# adapter_pcb.net
KiCad netlist of a schematic drawn in Altium Designer
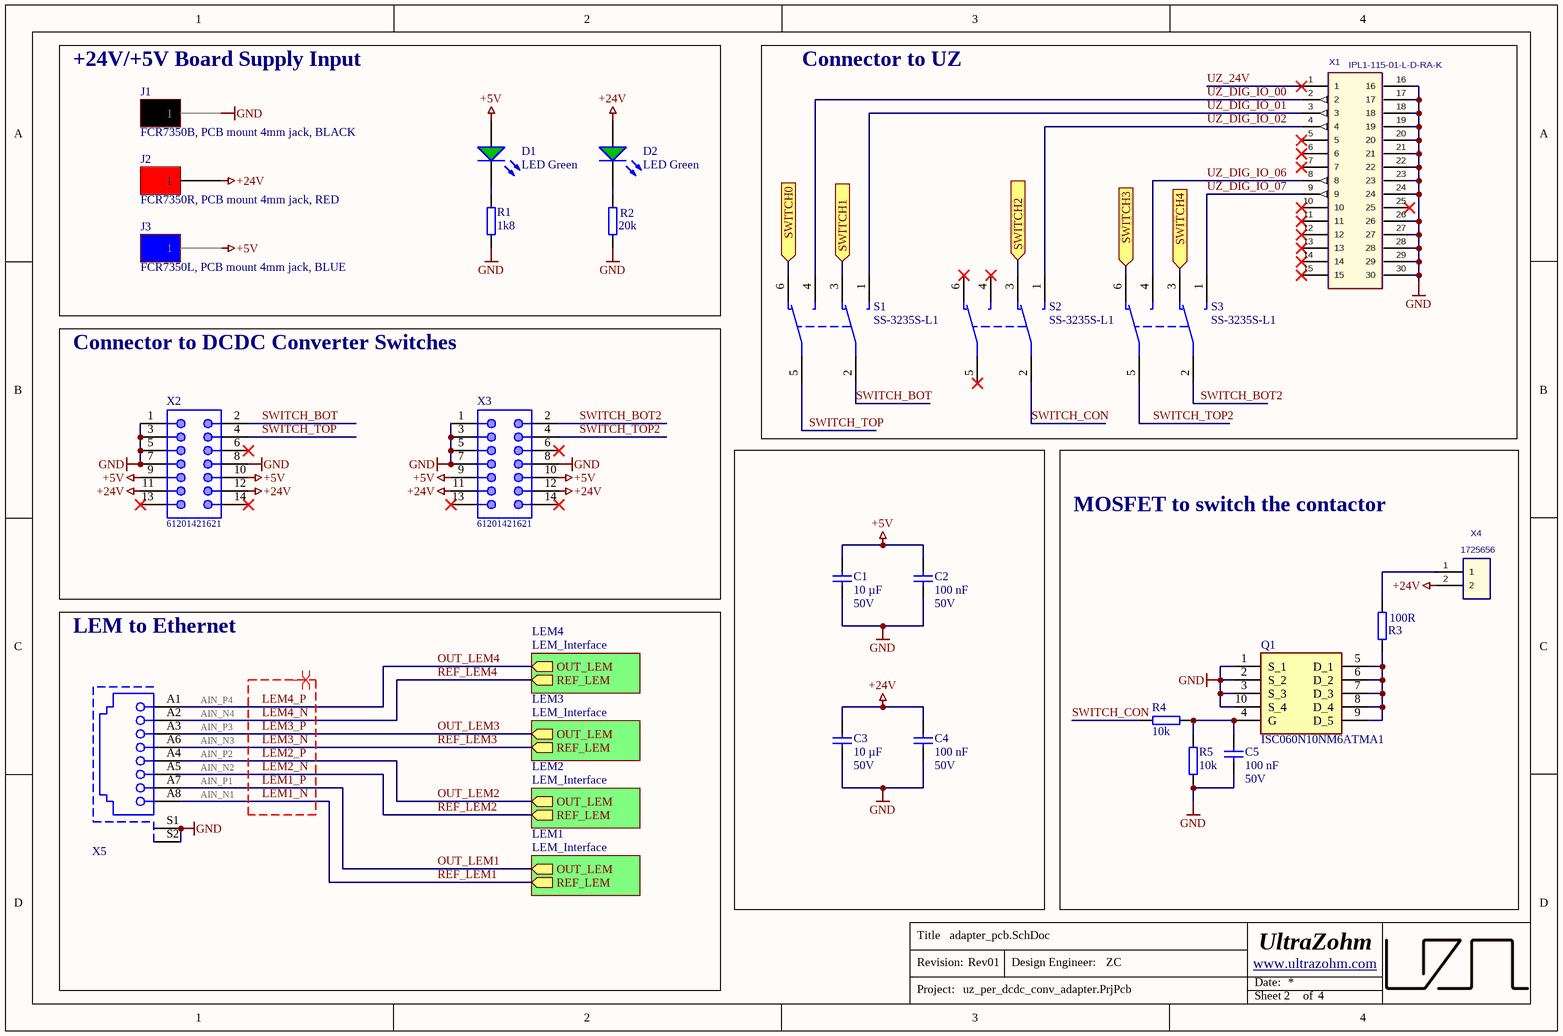
[diagram p0: adapter_pcb.SchDoc]

(export (version "E")
  (design (tool "Eeschema 10.0.6"))
  (components
    (comp (ref "C1")
      (value "10 µF")
      (footprint "C_1206_TE")
      (description "Generic capacitor")
      (fields
        (field (name "MANUFACTURER PART NUMBER") "UZgen_C_1206_10uF_50V_X7R")
        (field (name "MANUFACTURER") "UZgen")
        (field (name "VOLTAGE") "50V")
        (field (name "CREATED FROM") "MGeier")
      )
      (libsource (lib "user") (part "CAP-NP"))
    )
    (comp (ref "C2")
      (value "100 nF")
      (footprint "C_0603_TE")
      (description "Generic capacitor")
      (fields
        (field (name "MANUFACTURER PART NUMBER") "UZgen_C_0603_100nF_50V_X7R")
        (field (name "MANUFACTURER") "UZgen")
        (field (name "VOLTAGE") "50V")
        (field (name "CREATED FROM") "AGeiger")
      )
      (libsource (lib "user") (part "CAP-NP"))
    )
    (comp (ref "C3")
      (value "10 µF")
      (footprint "C_1206_TE")
      (description "Generic capacitor")
      (fields
        (field (name "MANUFACTURER PART NUMBER") "UZgen_C_1206_10uF_50V_X7R")
        (field (name "MANUFACTURER") "UZgen")
        (field (name "VOLTAGE") "50V")
        (field (name "CREATED FROM") "MGeier")
      )
      (libsource (lib "user") (part "CAP-NP"))
    )
    (comp (ref "C4")
      (value "100 nF")
      (footprint "C_0603_TE")
      (description "Generic capacitor")
      (fields
        (field (name "MANUFACTURER PART NUMBER") "UZgen_C_0603_100nF_50V_X7R")
        (field (name "MANUFACTURER") "UZgen")
        (field (name "VOLTAGE") "50V")
        (field (name "CREATED FROM") "AGeiger")
      )
      (libsource (lib "user") (part "CAP-NP"))
    )
    (comp (ref "C5")
      (value "100 nF")
      (footprint "C_0603_TE")
      (description "Generic capacitor")
      (fields
        (field (name "MANUFACTURER PART NUMBER") "UZgen_C_0603_100nF_50V_X7R")
        (field (name "MANUFACTURER") "UZgen")
        (field (name "VOLTAGE") "50V")
        (field (name "CREATED FROM") "AGeiger")
      )
      (libsource (lib "user") (part "CAP-NP"))
    )
    (comp (ref "D1")
      (value "LED Green")
      (footprint "WL-SMCW_0603")
      (description "LED GREEN 520~535NM 112~258MCD@20MA TOP VIEW 0603 ROHS")
      (fields
        (field (name "MANUFACTURER PART NUMBER") "19-217/GHC-YR1S2/3T")
        (field (name "MANUFACTURER") "Everlight Elec")
        (field (name "CREATED FROM") "T. Wendt")
      )
      (libsource (lib "user") (part "LED_Green"))
    )
    (comp (ref "D2")
      (value "LED Green")
      (footprint "WL-SMCW_0603")
      (description "LED GREEN 520~535NM 112~258MCD@20MA TOP VIEW 0603 ROHS")
      (fields
        (field (name "MANUFACTURER PART NUMBER") "19-217/GHC-YR1S2/3T")
        (field (name "MANUFACTURER") "Everlight Elec")
        (field (name "CREATED FROM") "T. Wendt")
      )
      (libsource (lib "user") (part "LED_Green"))
    )
    (comp (ref "J1")
      (value "FCR7350B, PCB mount 4mm jack, BLACK")
      (footprint "FCR7350")
      (description "FCR7350B, 1000V, 24A, BLACK")
      (fields
        (field (name "MANUFACTURER PART NUMBER") "FCR7350B")
        (field (name "MANUFACTURER") "Cliff")
        (field (name "CREATED FROM") "DHufnagel")
      )
      (libsource (lib "user") (part "FCR7350B"))
    )
    (comp (ref "J2")
      (value "FCR7350R, PCB mount 4mm jack, RED")
      (footprint "FCR7350")
      (description "FCR7350B, 1000V, 24A, RED")
      (fields
        (field (name "MANUFACTURER PART NUMBER") "FCR7350R")
        (field (name "MANUFACTURER") "Cliff")
        (field (name "CREATED FROM") "DHufnagel")
      )
      (libsource (lib "user") (part "FCR7350R"))
    )
    (comp (ref "J3")
      (value "FCR7350L, PCB mount 4mm jack, BLUE")
      (footprint "FCR7350")
      (description "FCR7350B, 1000V, 24A, BLUE")
      (fields
        (field (name "MANUFACTURER PART NUMBER") "FCR7350L")
        (field (name "MANUFACTURER") "Cliff")
        (field (name "CREATED FROM") "DHufnagel")
      )
      (libsource (lib "user") (part "FCR7350L"))
    )
    (comp (ref "Q1")
      (value "ISC060N10NM6ATMA1")
      (footprint "ISC060N10NM6ATMA1")
      (description "Power MOSFET, n-Channel, 97A, 100V")
      (fields
        (field (name "MANUFACTURER") "Infineon Technologies")
        (field (name "LCSC PART NUMBER") "C3288847")
        (field (name "CREATED FROM") "DHufnagel")
      )
      (libsource (lib "user") (part "ISC060N10NM6ATMA1"))
    )
    (comp (ref "R1")
      (value "1k8")
      (footprint "R_0603_TE")
      (description "Generic resistor")
      (fields
        (field (name "MANUFACTURER PART NUMBER") "UZgen_R_0603_1k8")
        (field (name "MANUFACTURER") "UZgen")
        (field (name "CREATED FROM") "UZgenTool")
      )
      (libsource (lib "user") (part "RES"))
    )
    (comp (ref "R2")
      (value "20k")
      (footprint "R_0603_TE")
      (description "Generic resistor")
      (fields
        (field (name "MANUFACTURER PART NUMBER") "UZgen_R_0603_20k")
        (field (name "MANUFACTURER") "UZgen")
        (field (name "CREATED FROM") "UZgenTool")
      )
      (libsource (lib "user") (part "RES"))
    )
    (comp (ref "R3")
      (value "100R")
      (footprint "R_0603_TE")
      (description "Generic resistor")
      (fields
        (field (name "MANUFACTURER PART NUMBER") "UZgen_R_0603_100R")
        (field (name "MANUFACTURER") "UZgen")
        (field (name "CREATED FROM") "UZgenTool")
      )
      (libsource (lib "user") (part "RES"))
    )
    (comp (ref "R4")
      (value "10k")
      (footprint "R_0603_TE")
      (description "Generic resistor")
      (fields
        (field (name "MANUFACTURER PART NUMBER") "UZgen_R_0603_10k")
        (field (name "MANUFACTURER") "UZgen")
        (field (name "CREATED FROM") "AGeiger")
      )
      (libsource (lib "user") (part "RES"))
    )
    (comp (ref "R5")
      (value "10k")
      (footprint "R_0603_TE")
      (description "Generic resistor")
      (fields
        (field (name "MANUFACTURER PART NUMBER") "UZgen_R_0603_10k")
        (field (name "MANUFACTURER") "UZgen")
        (field (name "CREATED FROM") "AGeiger")
      )
      (libsource (lib "user") (part "RES"))
    )
    (comp (ref "S1")
      (value "SS-3235S-L1")
      (footprint "SS-3235S-L1")
      (description "50mA Horizontal attachment DPDT 12V 12V 50mA 10,000 times Black SMD Slide Switches ROHS")
      (fields
        (field (name "MANUFACTURER") "XKB Connection")
        (field (name "LCSC PART NUMBER") "C500055")
        (field (name "CREATED FROM") "AGeiger")
      )
      (libsource (lib "user") (part "SS-3235S-L1"))
    )
    (comp (ref "S2")
      (value "SS-3235S-L1")
      (footprint "SS-3235S-L1")
      (description "50mA Horizontal attachment DPDT 12V 12V 50mA 10,000 times Black SMD Slide Switches ROHS")
      (fields
        (field (name "MANUFACTURER") "XKB Connection")
        (field (name "LCSC PART NUMBER") "C500055")
        (field (name "CREATED FROM") "AGeiger")
      )
      (libsource (lib "user") (part "SS-3235S-L1"))
    )
    (comp (ref "S3")
      (value "SS-3235S-L1")
      (footprint "SS-3235S-L1")
      (description "50mA Horizontal attachment DPDT 12V 12V 50mA 10,000 times Black SMD Slide Switches ROHS")
      (fields
        (field (name "MANUFACTURER") "XKB Connection")
        (field (name "LCSC PART NUMBER") "C500055")
        (field (name "CREATED FROM") "AGeiger")
      )
      (libsource (lib "user") (part "SS-3235S-L1"))
    )
    (comp (ref "X1")
      (value "IPL1-115-01-L-D-RA-K")
      (footprint "IPL1-115-01-XX-D-RA")
      (description "Terminal Assembly, Double Row, Right Angle, Thru-Hole, 2.54 mm x 2.54 mm Pitch, 30 Pins")
      (fields
        (field (name "MANUFACTURER") "SAMTEC")
        (field (name "LCSC PART NUMBER") "C7423882")
        (field (name "CREATED FROM") "TWendt")
      )
      (libsource (lib "user") (part "IPL1-115-01-XX-D-XX"))
    )
    (comp (ref "X2")
      (value "61201421621")
      (footprint "61201421621")
      (description "2.54mm Double Row 14-pol Vertical Male Pin Box Header")
      (fields (field (name "MANUFACTURER") "Wurth") (field (name "CREATED FROM") "TWilfling"))
      (libsource (lib "user") (part "61201421621"))
    )
    (comp (ref "X3")
      (value "61201421621")
      (footprint "61201421621")
      (description "2.54mm Double Row 14-pol Vertical Male Pin Box Header")
      (fields (field (name "MANUFACTURER") "Wurth") (field (name "CREATED FROM") "TWilfling"))
      (libsource (lib "user") (part "61201421621"))
    )
    (comp (ref "X4")
      (value "1725656")
      (footprint "1725656")
      (description "Fixed Mounting Block, 2 Pins, 2.54mm Pitch")
      (fields (field (name "MANUFACTURER") "Phoenix Contact") (field (name "CREATED FROM") "MGremer"))
      (libsource (lib "user") (part "IPL1-102-XX-X-S-X"))
    )
    (comp (ref "X5")
      (value "~")
      (footprint "R-RJ45R10P-B000")
      (fields
        (field (name "MANUFACTURER PART NUMBER") "R-RJ45R10P-B000")
        (field (name "MANUFACTURER") "Ckmtw(Shenzhen Cankemeng)")
        (field (name "LCSC PART NUMBER") "C386758")
        (field (name "CREATED FROM") "KIlhan")
      )
      (libsource (lib "user") (part "R-RJ45R10P-B000"))
    )
  )
  (nets
    (net (code "1") (name "+5V") (class "Default")
      (node (ref "C1") (pin "2") (pinfunction "2_2") (pintype "passive"))
      (node (ref "C2") (pin "2") (pinfunction "2_2") (pintype "passive"))
      (node (ref "D1") (pin "2") (pinfunction "A_2") (pintype "passive"))
      (node (ref "J3") (pin "1") (pinfunction "1_1") (pintype "passive"))
      (node (ref "X2") (pin "10") (pinfunction "10_10") (pintype "passive"))
      (node (ref "X2") (pin "9") (pinfunction "9_9") (pintype "passive"))
      (node (ref "X3") (pin "10") (pinfunction "10_10") (pintype "passive"))
      (node (ref "X3") (pin "9") (pinfunction "9_9") (pintype "passive"))
    )
    (net (code "2") (name "+24V") (class "Default")
      (node (ref "C3") (pin "2") (pinfunction "2_2") (pintype "passive"))
      (node (ref "C4") (pin "2") (pinfunction "2_2") (pintype "passive"))
      (node (ref "D2") (pin "2") (pinfunction "A_2") (pintype "passive"))
      (node (ref "J2") (pin "1") (pinfunction "1_1") (pintype "passive"))
      (node (ref "X2") (pin "11") (pinfunction "11_11") (pintype "passive"))
      (node (ref "X2") (pin "12") (pinfunction "12_12") (pintype "passive"))
      (node (ref "X3") (pin "11") (pinfunction "11_11") (pintype "passive"))
      (node (ref "X3") (pin "12") (pinfunction "12_12") (pintype "passive"))
      (node (ref "X4") (pin "2") (pinfunction "2_2") (pintype "passive"))
    )
    (net (code "3") (name "/LEM1_N") (class "Default")
      (node (ref "X5") (pin "A8") (pinfunction "A8_A8") (pintype "passive"))
    )
    (net (code "4") (name "/LEM1_P") (class "Default")
      (node (ref "X5") (pin "A7") (pinfunction "A7_A7") (pintype "passive"))
    )
    (net (code "5") (name "/LEM2_N") (class "Default")
      (node (ref "X5") (pin "A5") (pinfunction "A5_A5") (pintype "passive"))
    )
    (net (code "6") (name "/LEM2_P") (class "Default")
      (node (ref "X5") (pin "A4") (pinfunction "A4_A4") (pintype "passive"))
    )
    (net (code "7") (name "/LEM3_N") (class "Default")
      (node (ref "X5") (pin "A6") (pinfunction "A6_A6") (pintype "passive"))
    )
    (net (code "8") (name "/LEM3_P") (class "Default")
      (node (ref "X5") (pin "A3") (pinfunction "A3_A3") (pintype "passive"))
    )
    (net (code "9") (name "/LEM4_N") (class "Default")
      (node (ref "X5") (pin "A2") (pinfunction "A2_A2") (pintype "passive"))
    )
    (net (code "10") (name "/LEM4_P") (class "Default")
      (node (ref "X5") (pin "A1") (pinfunction "A1_A1") (pintype "passive"))
    )
    (net (code "11") (name "/SWITCH0") (class "Default")
      (node (ref "S1") (pin "6") (pinfunction "NC2_6") (pintype "passive"))
    )
    (net (code "12") (name "/SWITCH1") (class "Default")
      (node (ref "S1") (pin "3") (pinfunction "NC1_3") (pintype "passive"))
    )
    (net (code "13") (name "/SWITCH2") (class "Default")
      (node (ref "S2") (pin "3") (pinfunction "NC1_3") (pintype "passive"))
    )
    (net (code "14") (name "/SWITCH3") (class "Default")
      (node (ref "S3") (pin "6") (pinfunction "NC2_6") (pintype "passive"))
    )
    (net (code "15") (name "/SWITCH4") (class "Default")
      (node (ref "S3") (pin "3") (pinfunction "NC1_3") (pintype "passive"))
    )
    (net (code "16") (name "/SWITCH_BOT") (class "Default")
      (node (ref "S1") (pin "2") (pinfunction "COM1_2") (pintype "passive"))
      (node (ref "X2") (pin "2") (pinfunction "2_2") (pintype "passive"))
    )
    (net (code "17") (name "/SWITCH_BOT2") (class "Default")
      (node (ref "S3") (pin "2") (pinfunction "COM1_2") (pintype "passive"))
      (node (ref "X3") (pin "2") (pinfunction "2_2") (pintype "passive"))
    )
    (net (code "18") (name "/SWITCH_CON") (class "Default")
      (node (ref "R4") (pin "2") (pinfunction "2_2") (pintype "passive"))
      (node (ref "S2") (pin "2") (pinfunction "COM1_2") (pintype "passive"))
    )
    (net (code "19") (name "/SWITCH_TOP") (class "Default")
      (node (ref "S1") (pin "5") (pinfunction "COM2_5") (pintype "passive"))
      (node (ref "X2") (pin "4") (pinfunction "4_4") (pintype "passive"))
    )
    (net (code "20") (name "/SWITCH_TOP2") (class "Default")
      (node (ref "S3") (pin "5") (pinfunction "COM2_5") (pintype "passive"))
      (node (ref "X3") (pin "4") (pinfunction "4_4") (pintype "passive"))
    )
    (net (code "21") (name "/UZ_24V") (class "Default")
      (node (ref "X1") (pin "1") (pinfunction "1_1") (pintype "passive+no_connect"))
    )
    (net (code "22") (name "/UZ_DIG_IO_00") (class "Default")
      (node (ref "S1") (pin "4") (pinfunction "NO2_4") (pintype "passive"))
      (node (ref "X1") (pin "2") (pinfunction "2_2") (pintype "output"))
    )
    (net (code "23") (name "/UZ_DIG_IO_01") (class "Default")
      (node (ref "S1") (pin "1") (pinfunction "NO1_1") (pintype "passive"))
      (node (ref "X1") (pin "3") (pinfunction "3_3") (pintype "output"))
    )
    (net (code "24") (name "/UZ_DIG_IO_02") (class "Default")
      (node (ref "S2") (pin "1") (pinfunction "NO1_1") (pintype "passive"))
      (node (ref "X1") (pin "4") (pinfunction "4_4") (pintype "output"))
    )
    (net (code "25") (name "/UZ_DIG_IO_06") (class "Default")
      (node (ref "S3") (pin "4") (pinfunction "NO2_4") (pintype "passive"))
      (node (ref "X1") (pin "8") (pinfunction "8_8") (pintype "output"))
    )
    (net (code "26") (name "/UZ_DIG_IO_07") (class "Default")
      (node (ref "S3") (pin "1") (pinfunction "NO1_1") (pintype "passive"))
      (node (ref "X1") (pin "9") (pinfunction "9_9") (pintype "output"))
    )
    (net (code "27") (name "GND") (class "Default")
      (node (ref "C1") (pin "1") (pinfunction "1_1") (pintype "passive"))
      (node (ref "C2") (pin "1") (pinfunction "1_1") (pintype "passive"))
      (node (ref "C3") (pin "1") (pinfunction "1_1") (pintype "passive"))
      (node (ref "C4") (pin "1") (pinfunction "1_1") (pintype "passive"))
      (node (ref "C5") (pin "1") (pinfunction "1_1") (pintype "passive"))
      (node (ref "J1") (pin "1") (pinfunction "1_1") (pintype "passive"))
      (node (ref "Q1") (pin "1") (pinfunction "S_1_1") (pintype "passive"))
      (node (ref "Q1") (pin "10") (pinfunction "S_4_10") (pintype "passive"))
      (node (ref "Q1") (pin "2") (pinfunction "S_2_2") (pintype "passive"))
      (node (ref "Q1") (pin "3") (pinfunction "S_3_3") (pintype "passive"))
      (node (ref "R1") (pin "2") (pinfunction "2_2") (pintype "passive"))
      (node (ref "R2") (pin "2") (pinfunction "2_2") (pintype "passive"))
      (node (ref "R5") (pin "1") (pinfunction "1_1") (pintype "passive"))
      (node (ref "X1") (pin "16") (pinfunction "16_16") (pintype "passive"))
      (node (ref "X1") (pin "17") (pinfunction "17_17") (pintype "passive"))
      (node (ref "X1") (pin "18") (pinfunction "18_18") (pintype "passive"))
      (node (ref "X1") (pin "19") (pinfunction "19_19") (pintype "passive"))
      (node (ref "X1") (pin "20") (pinfunction "20_20") (pintype "passive"))
      (node (ref "X1") (pin "21") (pinfunction "21_21") (pintype "passive"))
      (node (ref "X1") (pin "22") (pinfunction "22_22") (pintype "passive"))
      (node (ref "X1") (pin "23") (pinfunction "23_23") (pintype "passive"))
      (node (ref "X1") (pin "24") (pinfunction "24_24") (pintype "passive"))
      (node (ref "X1") (pin "26") (pinfunction "26_26") (pintype "passive"))
      (node (ref "X1") (pin "27") (pinfunction "27_27") (pintype "passive"))
      (node (ref "X1") (pin "28") (pinfunction "28_28") (pintype "passive"))
      (node (ref "X1") (pin "29") (pinfunction "29_29") (pintype "passive"))
      (node (ref "X1") (pin "30") (pinfunction "30_30") (pintype "passive"))
      (node (ref "X2") (pin "1") (pinfunction "1_1") (pintype "passive"))
      (node (ref "X2") (pin "3") (pinfunction "3_3") (pintype "passive"))
      (node (ref "X2") (pin "5") (pinfunction "5_5") (pintype "passive"))
      (node (ref "X2") (pin "7") (pinfunction "7_7") (pintype "passive"))
      (node (ref "X2") (pin "8") (pinfunction "8_8") (pintype "passive"))
      (node (ref "X3") (pin "1") (pinfunction "1_1") (pintype "passive"))
      (node (ref "X3") (pin "3") (pinfunction "3_3") (pintype "passive"))
      (node (ref "X3") (pin "5") (pinfunction "5_5") (pintype "passive"))
      (node (ref "X3") (pin "7") (pinfunction "7_7") (pintype "passive"))
      (node (ref "X3") (pin "8") (pinfunction "8_8") (pintype "passive"))
      (node (ref "X5") (pin "S1") (pinfunction "S1_S1") (pintype "passive"))
      (node (ref "X5") (pin "S2") (pinfunction "S2_S2") (pintype "passive"))
    )
    (net (code "28") (name "Net-(D1-K)") (class "Default")
      (node (ref "D1") (pin "1") (pinfunction "K_1") (pintype "passive"))
      (node (ref "R1") (pin "1") (pinfunction "1_1") (pintype "passive"))
    )
    (net (code "29") (name "Net-(D2-K)") (class "Default")
      (node (ref "D2") (pin "1") (pinfunction "K_1") (pintype "passive"))
      (node (ref "R2") (pin "1") (pinfunction "1_1") (pintype "passive"))
    )
    (net (code "30") (name "Net-(Q1-D_1)") (class "Default")
      (node (ref "Q1") (pin "5") (pinfunction "D_1_5") (pintype "passive"))
      (node (ref "Q1") (pin "6") (pinfunction "D_2_6") (pintype "passive"))
      (node (ref "Q1") (pin "7") (pinfunction "D_3_7") (pintype "passive"))
      (node (ref "Q1") (pin "8") (pinfunction "D_4_8") (pintype "passive"))
      (node (ref "Q1") (pin "9") (pinfunction "D_5_9") (pintype "passive"))
      (node (ref "R3") (pin "2") (pinfunction "2_2") (pintype "passive"))
    )
    (net (code "31") (name "Net-(Q1-G)") (class "Default")
      (node (ref "C5") (pin "2") (pinfunction "2_2") (pintype "passive"))
      (node (ref "Q1") (pin "4") (pinfunction "G_4") (pintype "passive"))
      (node (ref "R4") (pin "1") (pinfunction "1_1") (pintype "passive"))
      (node (ref "R5") (pin "2") (pinfunction "2_2") (pintype "passive"))
    )
    (net (code "32") (name "Net-(R3-Pad1)") (class "Default")
      (node (ref "R3") (pin "1") (pinfunction "1_1") (pintype "passive"))
      (node (ref "X4") (pin "1") (pinfunction "1_1") (pintype "passive"))
    )
    (net (code "33") (name "unconnected-(S2-COM2-Pad5)") (class "Default")
      (node (ref "S2") (pin "5") (pinfunction "COM2_5") (pintype "passive+no_connect"))
    )
    (net (code "34") (name "unconnected-(S2-NC2-Pad6)") (class "Default")
      (node (ref "S2") (pin "6") (pinfunction "NC2_6") (pintype "passive+no_connect"))
    )
    (net (code "35") (name "unconnected-(S2-NO2-Pad4)") (class "Default")
      (node (ref "S2") (pin "4") (pinfunction "NO2_4") (pintype "passive+no_connect"))
    )
    (net (code "36") (name "unconnected-(X1-Pad5)") (class "Default")
      (node (ref "X1") (pin "5") (pinfunction "5_5") (pintype "passive+no_connect"))
    )
    (net (code "37") (name "unconnected-(X1-Pad6)") (class "Default")
      (node (ref "X1") (pin "6") (pinfunction "6_6") (pintype "passive+no_connect"))
    )
    (net (code "38") (name "unconnected-(X1-Pad7)") (class "Default")
      (node (ref "X1") (pin "7") (pinfunction "7_7") (pintype "passive+no_connect"))
    )
    (net (code "39") (name "unconnected-(X1-Pad10)") (class "Default")
      (node (ref "X1") (pin "10") (pinfunction "10_10") (pintype "passive+no_connect"))
    )
    (net (code "40") (name "unconnected-(X1-Pad11)") (class "Default")
      (node (ref "X1") (pin "11") (pinfunction "11_11") (pintype "passive+no_connect"))
    )
    (net (code "41") (name "unconnected-(X1-Pad12)") (class "Default")
      (node (ref "X1") (pin "12") (pinfunction "12_12") (pintype "passive+no_connect"))
    )
    (net (code "42") (name "unconnected-(X1-Pad13)") (class "Default")
      (node (ref "X1") (pin "13") (pinfunction "13_13") (pintype "passive+no_connect"))
    )
    (net (code "43") (name "unconnected-(X1-Pad14)") (class "Default")
      (node (ref "X1") (pin "14") (pinfunction "14_14") (pintype "passive+no_connect"))
    )
    (net (code "44") (name "unconnected-(X1-Pad15)") (class "Default")
      (node (ref "X1") (pin "15") (pinfunction "15_15") (pintype "passive+no_connect"))
    )
    (net (code "45") (name "unconnected-(X1-Pad25)") (class "Default")
      (node (ref "X1") (pin "25") (pinfunction "25_25") (pintype "passive+no_connect"))
    )
    (net (code "46") (name "unconnected-(X2-Pad6)") (class "Default")
      (node (ref "X2") (pin "6") (pinfunction "6_6") (pintype "passive+no_connect"))
    )
    (net (code "47") (name "unconnected-(X2-Pad13)") (class "Default")
      (node (ref "X2") (pin "13") (pinfunction "13_13") (pintype "passive+no_connect"))
    )
    (net (code "48") (name "unconnected-(X2-Pad14)") (class "Default")
      (node (ref "X2") (pin "14") (pinfunction "14_14") (pintype "passive+no_connect"))
    )
    (net (code "49") (name "unconnected-(X3-Pad6)") (class "Default")
      (node (ref "X3") (pin "6") (pinfunction "6_6") (pintype "passive+no_connect"))
    )
    (net (code "50") (name "unconnected-(X3-Pad13)") (class "Default")
      (node (ref "X3") (pin "13") (pinfunction "13_13") (pintype "passive+no_connect"))
    )
    (net (code "51") (name "unconnected-(X3-Pad14)") (class "Default")
      (node (ref "X3") (pin "14") (pinfunction "14_14") (pintype "passive+no_connect"))
    )
  )
)
